# schematic_full.net
KiCad netlist of a schematic drawn in EAGLE
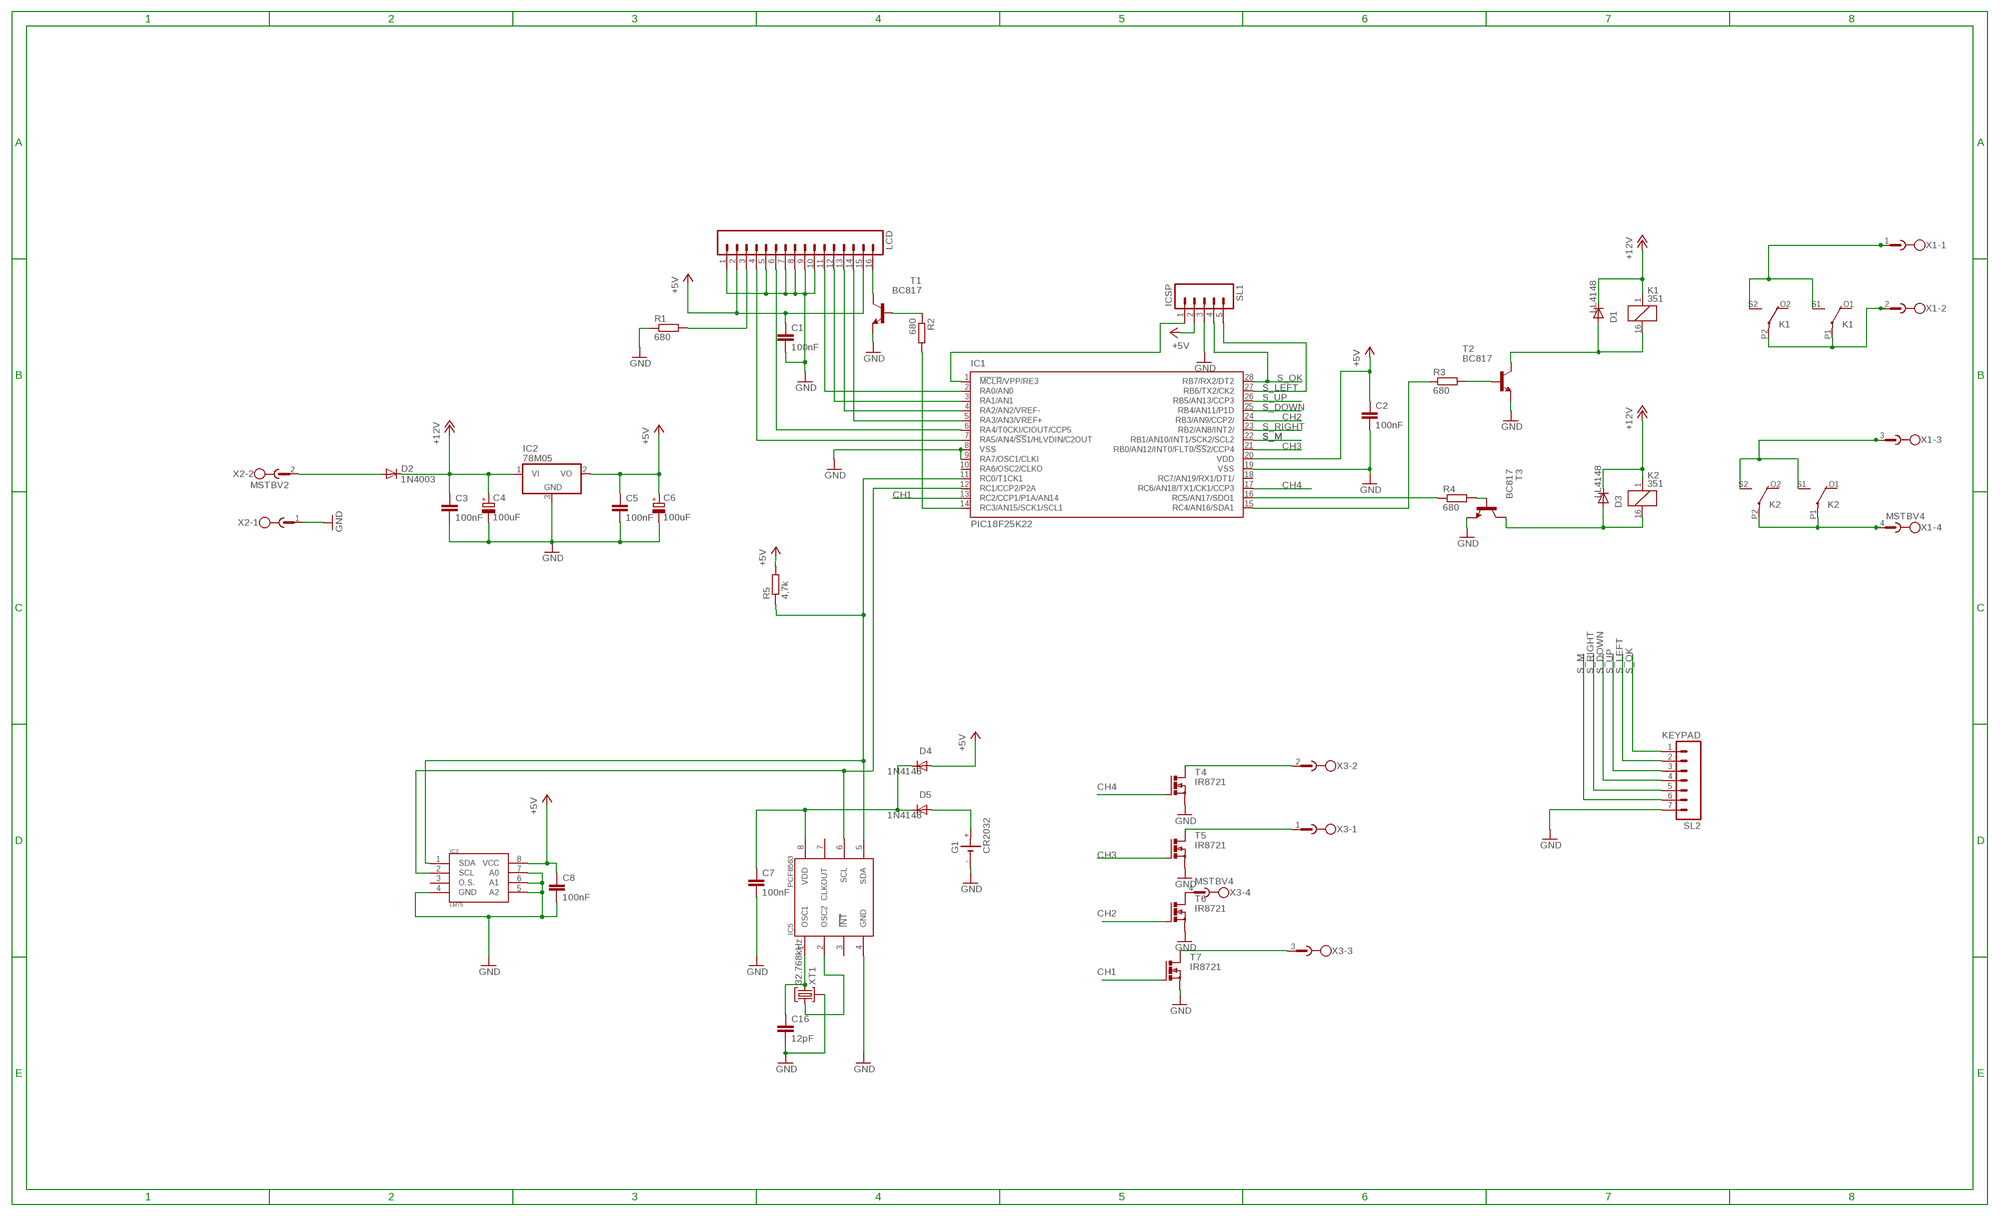
[diagram p0: schematic, sheet 1]

(export (version "E")
  (design (tool "Eeschema 10.0.6"))
  (components
    (comp (ref "C1")
      (value "100nF")
      (footprint "eagle-import:C0805K")
      (libsource (lib "eagle-import") (part "C-EUC0805K"))
    )
    (comp (ref "C2")
      (value "100nF")
      (footprint "eagle-import:C0805K")
      (libsource (lib "eagle-import") (part "C-EUC0805K"))
    )
    (comp (ref "C3")
      (value "100nF")
      (footprint "eagle-import:C0805K")
      (libsource (lib "eagle-import") (part "C-EUC0805K"))
    )
    (comp (ref "C4")
      (value "100uF")
      (footprint "eagle-import:E2,5-6E")
      (libsource (lib "eagle-import") (part "CPOL-EUE2,5-6E"))
    )
    (comp (ref "C5")
      (value "100nF")
      (footprint "eagle-import:C0805K")
      (libsource (lib "eagle-import") (part "C-EUC0805K"))
    )
    (comp (ref "C6")
      (value "100uF")
      (footprint "eagle-import:E2,5-6")
      (libsource (lib "eagle-import") (part "CPOL-EUE2.5-6"))
    )
    (comp (ref "C7")
      (value "100nF")
      (footprint "eagle-import:C0805K")
      (libsource (lib "eagle-import") (part "C-EUC0805K"))
    )
    (comp (ref "C8")
      (value "100nF")
      (footprint "eagle-import:C0805K")
      (libsource (lib "eagle-import") (part "C-EUC0805K"))
    )
    (comp (ref "C16")
      (value "12pF")
      (footprint "eagle-import:C0805K")
      (libsource (lib "eagle-import") (part "C-EUC0805K"))
    )
    (comp (ref "D1")
      (value "LL4148")
      (footprint "eagle-import:DO214BA")
      (libsource (lib "eagle-import") (part "DIODE-DO214BA"))
    )
    (comp (ref "D2")
      (value "1N4003")
      (footprint "eagle-import:DO41-10")
      (libsource (lib "eagle-import") (part "1N4933"))
    )
    (comp (ref "D3")
      (value "LL4148")
      (footprint "eagle-import:DO214BA")
      (libsource (lib "eagle-import") (part "DIODE-DO214BA"))
    )
    (comp (ref "D4")
      (value "1N4148")
      (footprint "eagle-import:DO214BA")
      (libsource (lib "eagle-import") (part "DIODE-DO214BA"))
    )
    (comp (ref "D5")
      (value "1N4148")
      (footprint "eagle-import:DO214BA")
      (libsource (lib "eagle-import") (part "DIODE-DO214BA"))
    )
    (comp (ref "G1")
      (value "CR2032")
      (footprint "eagle-import:CR2032")
      (libsource (lib "eagle-import") (part "CR2032"))
    )
    (comp (ref "IC1")
      (value "PIC18F25K22")
      (footprint "eagle-import:SSOP28")
      (libsource (lib "eagle-import") (part "PIC18F25K22/SS-E"))
    )
    (comp (ref "IC2")
      (value "78M05")
      (footprint "eagle-import:TO252")
      (libsource (lib "eagle-import") (part "78DT05"))
    )
    (comp (ref "IC3")
      (value "LM75")
      (footprint "eagle-import:SO08")
      (libsource (lib "eagle-import") (part "LM75"))
    )
    (comp (ref "IC5")
      (value "PCF8563")
      (footprint "eagle-import:SO08")
      (libsource (lib "eagle-import") (part "PCF8563"))
    )
    (comp (ref "K1")
      (value "351")
      (footprint "eagle-import:351")
      (libsource (lib "eagle-import") (part "351"))
    )
    (comp (ref "K2")
      (value "351")
      (footprint "eagle-import:351")
      (libsource (lib "eagle-import") (part "351"))
    )
    (comp (ref "LCD")
      (value "M16")
      (footprint "eagle-import:16P")
      (libsource (lib "eagle-import") (part "M16"))
    )
    (comp (ref "R1")
      (value "680")
      (footprint "eagle-import:M0805")
      (libsource (lib "eagle-import") (part "R-EU_M0805"))
    )
    (comp (ref "R2")
      (value "680")
      (footprint "eagle-import:M0805")
      (libsource (lib "eagle-import") (part "R-EU_M0805"))
    )
    (comp (ref "R3")
      (value "680")
      (footprint "eagle-import:M0805")
      (libsource (lib "eagle-import") (part "R-EU_M0805"))
    )
    (comp (ref "R4")
      (value "680")
      (footprint "eagle-import:M0805")
      (libsource (lib "eagle-import") (part "R-EU_M0805"))
    )
    (comp (ref "R5")
      (value "4,7k")
      (footprint "eagle-import:M0805")
      (libsource (lib "eagle-import") (part "R-EU_M0805"))
    )
    (comp (ref "SL1")
      (value "ICSP")
      (footprint "eagle-import:05P")
      (libsource (lib "eagle-import") (part "M05"))
    )
    (comp (ref "SL2")
      (value "KEYPAD")
      (footprint "eagle-import:07PA")
      (libsource (lib "eagle-import") (part "MA07"))
    )
    (comp (ref "T1")
      (value "BC817")
      (footprint "eagle-import:SOT23-BEC")
      (libsource (lib "eagle-import") (part "BC817SMD-40"))
    )
    (comp (ref "T2")
      (value "BC817")
      (footprint "eagle-import:SOT23-BEC")
      (libsource (lib "eagle-import") (part "BC817SMD-40"))
    )
    (comp (ref "T3")
      (value "BC817")
      (footprint "eagle-import:SOT23-BEC")
      (libsource (lib "eagle-import") (part "BC817SMD-40"))
    )
    (comp (ref "T4")
      (value "IR8721")
      (footprint "eagle-import:TO252")
      (libsource (lib "eagle-import") (part "IRLR120N"))
    )
    (comp (ref "T5")
      (value "IR8721")
      (footprint "eagle-import:TO252")
      (libsource (lib "eagle-import") (part "IRLR120N"))
    )
    (comp (ref "T6")
      (value "IR8721")
      (footprint "eagle-import:TO252")
      (libsource (lib "eagle-import") (part "IRLR120N"))
    )
    (comp (ref "T7")
      (value "IR8721")
      (footprint "eagle-import:TO252")
      (libsource (lib "eagle-import") (part "IRLR120N"))
    )
    (comp (ref "X1")
      (value "MSTBV4")
      (footprint "eagle-import:MSTBV4")
      (fields (field (name "MPN") "MSTBV 2,5/4-GF-5.08"))
      (libsource (lib "eagle-import") (part "MSTBV4"))
    )
    (comp (ref "X2")
      (value "MSTBV2")
      (footprint "eagle-import:MSTBV2")
      (fields (field (name "MPN") "MSTBV 2,5/2-GF-5.08"))
      (libsource (lib "eagle-import") (part "MSTBV2"))
    )
    (comp (ref "X3")
      (value "MSTBV4")
      (footprint "eagle-import:MSTBV4")
      (fields (field (name "MPN") "MSTBV 2,5/4-GF-5.08"))
      (libsource (lib "eagle-import") (part "MSTBV4"))
    )
    (comp (ref "XT1")
      (value "32.768kHz")
      (footprint "eagle-import:XTMINI")
      (libsource (lib "eagle-import") (part "XTMINI"))
    )
  )
  (nets
    (net (code "1") (name "+5V") (class "Default")
      (node (ref "C1") (pin "1") (pinfunction "1_1") (pintype "passive"))
      (node (ref "C2") (pin "1") (pinfunction "1_1") (pintype "passive"))
      (node (ref "C5") (pin "1") (pinfunction "1_1") (pintype "passive"))
      (node (ref "C6") (pin "+") (pinfunction "+_+") (pintype "passive"))
      (node (ref "C8") (pin "1") (pinfunction "1_1") (pintype "passive"))
      (node (ref "D4") (pin "A") (pinfunction "A_A") (pintype "passive"))
      (node (ref "IC1") (pin "20") (pinfunction "VDD_20") (pintype "power_in"))
      (node (ref "IC2") (pin "2") (pinfunction "VO_2") (pintype "passive"))
      (node (ref "IC3") (pin "8") (pinfunction "VCC_8") (pintype "bidirectional"))
      (node (ref "LCD") (pin "15") (pinfunction "15_15") (pintype "passive"))
      (node (ref "LCD") (pin "2") (pinfunction "2_2") (pintype "passive"))
      (node (ref "R5") (pin "2") (pinfunction "2_2") (pintype "passive"))
      (node (ref "SL1") (pin "2") (pinfunction "2_2") (pintype "passive"))
    )
    (net (code "2") (name "+12V") (class "Default")
      (node (ref "C3") (pin "1") (pinfunction "1_1") (pintype "passive"))
      (node (ref "C4") (pin "+") (pinfunction "+_+") (pintype "passive"))
      (node (ref "D1") (pin "C") (pinfunction "C_C") (pintype "passive"))
      (node (ref "D2") (pin "C") (pinfunction "C_C") (pintype "passive"))
      (node (ref "D3") (pin "C") (pinfunction "C_C") (pintype "passive"))
      (node (ref "IC2") (pin "1") (pinfunction "VI_1") (pintype "input"))
      (node (ref "K1") (pin "1") (pinfunction "1_1") (pintype "passive"))
      (node (ref "K2") (pin "1") (pinfunction "1_1") (pintype "passive"))
    )
    (net (code "3") (name "/CH1") (class "Default")
      (node (ref "IC1") (pin "13") (pinfunction "RC2/CCP1/P1A/AN14_13") (pintype "bidirectional"))
      (node (ref "T7") (pin "1") (pinfunction "G_1") (pintype "passive"))
    )
    (net (code "4") (name "/CH2") (class "Default")
      (node (ref "IC1") (pin "24") (pinfunction "RB3/AN9/CCP2/_24") (pintype "bidirectional"))
      (node (ref "T6") (pin "1") (pinfunction "G_1") (pintype "passive"))
    )
    (net (code "5") (name "/CH3") (class "Default")
      (node (ref "IC1") (pin "21") (pinfunction "RB0/AN12/INT0/FLT0/~{SS}2/CCP4_21") (pintype "bidirectional"))
      (node (ref "T5") (pin "1") (pinfunction "G_1") (pintype "passive"))
    )
    (net (code "6") (name "/CH4") (class "Default")
      (node (ref "IC1") (pin "17") (pinfunction "RC6/AN18/TX1/CK1/CCP3_17") (pintype "bidirectional"))
      (node (ref "T4") (pin "1") (pinfunction "G_1") (pintype "passive"))
    )
    (net (code "7") (name "/S_DOWN") (class "Default")
      (node (ref "IC1") (pin "25") (pinfunction "RB4/AN11/P1D_25") (pintype "bidirectional"))
      (node (ref "SL2") (pin "4") (pinfunction "4_4") (pintype "passive"))
    )
    (net (code "8") (name "/S_LEFT") (class "Default")
      (node (ref "IC1") (pin "27") (pinfunction "RB6/TX2/CK2_27") (pintype "bidirectional"))
      (node (ref "SL1") (pin "5") (pinfunction "5_5") (pintype "passive"))
      (node (ref "SL2") (pin "2") (pinfunction "2_2") (pintype "passive"))
    )
    (net (code "9") (name "/S_M") (class "Default")
      (node (ref "IC1") (pin "22") (pinfunction "RB1/AN10/INT1/SCK2/SCL2_22") (pintype "bidirectional"))
      (node (ref "SL2") (pin "6") (pinfunction "6_6") (pintype "passive"))
    )
    (net (code "10") (name "/S_OK") (class "Default")
      (node (ref "IC1") (pin "28") (pinfunction "RB7/RX2/DT2_28") (pintype "bidirectional"))
      (node (ref "SL1") (pin "4") (pinfunction "4_4") (pintype "passive"))
      (node (ref "SL2") (pin "1") (pinfunction "1_1") (pintype "passive"))
    )
    (net (code "11") (name "/S_RIGHT") (class "Default")
      (node (ref "IC1") (pin "23") (pinfunction "RB2/AN8/INT2/_23") (pintype "bidirectional"))
      (node (ref "SL2") (pin "5") (pinfunction "5_5") (pintype "passive"))
    )
    (net (code "12") (name "/S_UP") (class "Default")
      (node (ref "IC1") (pin "26") (pinfunction "RB5/AN13/CCP3_26") (pintype "bidirectional"))
      (node (ref "SL2") (pin "3") (pinfunction "3_3") (pintype "passive"))
    )
    (net (code "13") (name "GND") (class "Default")
      (node (ref "C1") (pin "2") (pinfunction "2_2") (pintype "passive"))
      (node (ref "C16") (pin "2") (pinfunction "2_2") (pintype "passive"))
      (node (ref "C2") (pin "2") (pinfunction "2_2") (pintype "passive"))
      (node (ref "C3") (pin "2") (pinfunction "2_2") (pintype "passive"))
      (node (ref "C4") (pin "-") (pinfunction "-_-") (pintype "passive"))
      (node (ref "C5") (pin "2") (pinfunction "2_2") (pintype "passive"))
      (node (ref "C6") (pin "-") (pinfunction "-_-") (pintype "passive"))
      (node (ref "C7") (pin "2") (pinfunction "2_2") (pintype "passive"))
      (node (ref "C8") (pin "2") (pinfunction "2_2") (pintype "passive"))
      (node (ref "G1") (pin "-") (pinfunction "-_-") (pintype "passive"))
      (node (ref "IC1") (pin "19") (pinfunction "VSS_19") (pintype "power_in"))
      (node (ref "IC1") (pin "8") (pinfunction "VSS_8") (pintype "power_in"))
      (node (ref "IC1") (pin "9") (pinfunction "RA7/OSC1/CLKI_9") (pintype "input"))
      (node (ref "IC2") (pin "3") (pinfunction "GND_3") (pintype "passive"))
      (node (ref "IC3") (pin "4") (pinfunction "GND_4") (pintype "bidirectional"))
      (node (ref "IC3") (pin "5") (pinfunction "A2_5") (pintype "bidirectional"))
      (node (ref "IC3") (pin "6") (pinfunction "A1_6") (pintype "bidirectional"))
      (node (ref "IC3") (pin "7") (pinfunction "A0_7") (pintype "bidirectional"))
      (node (ref "IC5") (pin "4") (pinfunction "GND_4") (pintype "bidirectional"))
      (node (ref "LCD") (pin "1") (pinfunction "1_1") (pintype "passive"))
      (node (ref "LCD") (pin "10") (pinfunction "10_10") (pintype "passive"))
      (node (ref "LCD") (pin "5") (pinfunction "5_5") (pintype "passive"))
      (node (ref "LCD") (pin "7") (pinfunction "7_7") (pintype "passive"))
      (node (ref "LCD") (pin "8") (pinfunction "8_8") (pintype "passive"))
      (node (ref "LCD") (pin "9") (pinfunction "9_9") (pintype "passive"))
      (node (ref "R1") (pin "1") (pinfunction "1_1") (pintype "passive"))
      (node (ref "SL1") (pin "3") (pinfunction "3_3") (pintype "passive"))
      (node (ref "SL2") (pin "7") (pinfunction "7_7") (pintype "passive"))
      (node (ref "T1") (pin "E") (pinfunction "E_E") (pintype "passive"))
      (node (ref "T2") (pin "E") (pinfunction "E_E") (pintype "passive"))
      (node (ref "T3") (pin "E") (pinfunction "E_E") (pintype "passive"))
      (node (ref "T4") (pin "3") (pinfunction "S_3") (pintype "passive"))
      (node (ref "T5") (pin "3") (pinfunction "S_3") (pintype "passive"))
      (node (ref "T6") (pin "3") (pinfunction "S_3") (pintype "passive"))
      (node (ref "T7") (pin "3") (pinfunction "S_3") (pintype "passive"))
      (node (ref "X2") (pin "1") (pinfunction "1_1") (pintype "passive"))
      (node (ref "XT1") (pin "P$3") (pinfunction "3_P$3") (pintype "passive"))
    )
    (net (code "14") (name "Net-(D5-PadA)") (class "Default")
      (node (ref "D5") (pin "A") (pinfunction "A_A") (pintype "passive"))
      (node (ref "G1") (pin "+") (pinfunction "+_+") (pintype "passive"))
    )
    (net (code "15") (name "Net-(IC1-RA0{slash}AN0)") (class "Default")
      (node (ref "IC1") (pin "2") (pinfunction "RA0/AN0_2") (pintype "bidirectional"))
      (node (ref "LCD") (pin "11") (pinfunction "11_11") (pintype "passive"))
    )
    (net (code "16") (name "Net-(IC1-RA1{slash}AN1)") (class "Default")
      (node (ref "IC1") (pin "3") (pinfunction "RA1/AN1_3") (pintype "bidirectional"))
      (node (ref "LCD") (pin "12") (pinfunction "12_12") (pintype "passive"))
    )
    (net (code "17") (name "Net-(IC1-RA2{slash}AN2{slash}VREF-)") (class "Default")
      (node (ref "IC1") (pin "4") (pinfunction "RA2/AN2/VREF-_4") (pintype "bidirectional"))
      (node (ref "LCD") (pin "13") (pinfunction "13_13") (pintype "passive"))
    )
    (net (code "18") (name "Net-(IC1-RA3{slash}AN3{slash}VREF+)") (class "Default")
      (node (ref "IC1") (pin "5") (pinfunction "RA3/AN3/VREF+_5") (pintype "bidirectional"))
      (node (ref "LCD") (pin "14") (pinfunction "14_14") (pintype "passive"))
    )
    (net (code "19") (name "Net-(IC1-RA4{slash}T0CKI{slash}CIOUT{slash}CCP5)") (class "Default")
      (node (ref "IC1") (pin "6") (pinfunction "RA4/T0CKI/CIOUT/CCP5_6") (pintype "bidirectional"))
      (node (ref "LCD") (pin "6") (pinfunction "6_6") (pintype "passive"))
    )
    (net (code "20") (name "Net-(IC1-RA5{slash}AN4{slash}~{SS}1{slash}HLVDIN{slash}C2OUT)") (class "Default")
      (node (ref "IC1") (pin "7") (pinfunction "RA5/AN4/~{SS}1/HLVDIN/C2OUT_7") (pintype "bidirectional"))
      (node (ref "LCD") (pin "4") (pinfunction "4_4") (pintype "passive"))
    )
    (net (code "21") (name "Net-(IC1-RC0{slash}T1CK1)") (class "Default")
      (node (ref "IC1") (pin "11") (pinfunction "RC0/T1CK1_11") (pintype "bidirectional"))
      (node (ref "IC3") (pin "1") (pinfunction "SDA_1") (pintype "bidirectional"))
      (node (ref "IC5") (pin "5") (pinfunction "SDA_5") (pintype "bidirectional"))
      (node (ref "R5") (pin "1") (pinfunction "1_1") (pintype "passive"))
    )
    (net (code "22") (name "Net-(IC1-RC1{slash}CCP2{slash}P2A)") (class "Default")
      (node (ref "IC1") (pin "12") (pinfunction "RC1/CCP2/P2A_12") (pintype "bidirectional"))
      (node (ref "IC3") (pin "2") (pinfunction "SCL_2") (pintype "bidirectional"))
      (node (ref "IC5") (pin "6") (pinfunction "SCL_6") (pintype "bidirectional"))
    )
    (net (code "23") (name "Net-(IC1-RC3{slash}AN15{slash}SCK1{slash}SCL1)") (class "Default")
      (node (ref "IC1") (pin "14") (pinfunction "RC3/AN15/SCK1/SCL1_14") (pintype "bidirectional"))
      (node (ref "R2") (pin "2") (pinfunction "2_2") (pintype "passive"))
    )
    (net (code "24") (name "Net-(IC1-RC4{slash}AN16{slash}SDA1)") (class "Default")
      (node (ref "IC1") (pin "15") (pinfunction "RC4/AN16/SDA1_15") (pintype "bidirectional"))
      (node (ref "R3") (pin "1") (pinfunction "1_1") (pintype "passive"))
    )
    (net (code "25") (name "Net-(IC1-RC5{slash}AN17{slash}SDO1)") (class "Default")
      (node (ref "IC1") (pin "16") (pinfunction "RC5/AN17/SDO1_16") (pintype "bidirectional"))
      (node (ref "R4") (pin "1") (pinfunction "1_1") (pintype "passive"))
    )
    (net (code "26") (name "Net-(IC1-~{MCLR}{slash}VPP{slash}RE3)") (class "Default")
      (node (ref "IC1") (pin "1") (pinfunction "~{MCLR}/VPP/RE3_1") (pintype "input"))
      (node (ref "SL1") (pin "1") (pinfunction "1_1") (pintype "passive"))
    )
    (net (code "27") (name "Net-(IC5-OSC1)") (class "Default")
      (node (ref "C16") (pin "1") (pinfunction "1_1") (pintype "passive"))
      (node (ref "IC5") (pin "1") (pinfunction "OSC1_1") (pintype "bidirectional"))
      (node (ref "XT1") (pin "P$2") (pinfunction "2_P$2") (pintype "passive"))
    )
    (net (code "28") (name "Net-(IC5-OSC2)") (class "Default")
      (node (ref "IC5") (pin "2") (pinfunction "OSC2_2") (pintype "bidirectional"))
      (node (ref "XT1") (pin "P$1") (pinfunction "1_P$1") (pintype "passive"))
    )
    (net (code "29") (name "Net-(IC5-VDD)") (class "Default")
      (node (ref "C7") (pin "1") (pinfunction "1_1") (pintype "passive"))
      (node (ref "D4") (pin "C") (pinfunction "C_C") (pintype "passive"))
      (node (ref "D5") (pin "C") (pinfunction "C_C") (pintype "passive"))
      (node (ref "IC5") (pin "8") (pinfunction "VDD_8") (pintype "bidirectional"))
    )
    (net (code "30") (name "Net-(K1A-2)") (class "Default")
      (node (ref "D1") (pin "A") (pinfunction "A_A") (pintype "passive"))
      (node (ref "K1") (pin "16") (pinfunction "2_16") (pintype "passive"))
      (node (ref "T2") (pin "C") (pinfunction "C_C") (pintype "passive"))
    )
    (net (code "31") (name "Net-(K1B-P)") (class "Default")
      (node (ref "K1") (pin "P1") (pinfunction "P_P1") (pintype "passive"))
      (node (ref "K1") (pin "P2") (pinfunction "P_P2") (pintype "passive"))
      (node (ref "X1") (pin "2") (pinfunction "1_2") (pintype "passive"))
    )
    (net (code "32") (name "Net-(K1B-S)") (class "Default")
      (node (ref "K1") (pin "S1") (pinfunction "S_S1") (pintype "passive"))
      (node (ref "K1") (pin "S2") (pinfunction "S_S2") (pintype "passive"))
      (node (ref "X1") (pin "1") (pinfunction "1_1") (pintype "passive"))
    )
    (net (code "33") (name "Net-(K2A-2)") (class "Default")
      (node (ref "D3") (pin "A") (pinfunction "A_A") (pintype "passive"))
      (node (ref "K2") (pin "16") (pinfunction "2_16") (pintype "passive"))
      (node (ref "T3") (pin "C") (pinfunction "C_C") (pintype "passive"))
    )
    (net (code "34") (name "Net-(K2B-P)") (class "Default")
      (node (ref "K2") (pin "P1") (pinfunction "P_P1") (pintype "passive"))
      (node (ref "K2") (pin "P2") (pinfunction "P_P2") (pintype "passive"))
      (node (ref "X1") (pin "4") (pinfunction "1_4") (pintype "passive"))
    )
    (net (code "35") (name "Net-(K2B-S)") (class "Default")
      (node (ref "K2") (pin "S1") (pinfunction "S_S1") (pintype "passive"))
      (node (ref "K2") (pin "S2") (pinfunction "S_S2") (pintype "passive"))
      (node (ref "X1") (pin "3") (pinfunction "1_3") (pintype "passive"))
    )
    (net (code "36") (name "Net-(LCD-Pad3)") (class "Default")
      (node (ref "LCD") (pin "3") (pinfunction "3_3") (pintype "passive"))
      (node (ref "R1") (pin "2") (pinfunction "2_2") (pintype "passive"))
    )
    (net (code "37") (name "Net-(LCD-Pad16)") (class "Default")
      (node (ref "LCD") (pin "16") (pinfunction "16_16") (pintype "passive"))
      (node (ref "T1") (pin "C") (pinfunction "C_C") (pintype "passive"))
    )
    (net (code "38") (name "Net-(R2-Pad1)") (class "Default")
      (node (ref "R2") (pin "1") (pinfunction "1_1") (pintype "passive"))
      (node (ref "T1") (pin "B") (pinfunction "B_B") (pintype "passive"))
    )
    (net (code "39") (name "Net-(R3-Pad2)") (class "Default")
      (node (ref "R3") (pin "2") (pinfunction "2_2") (pintype "passive"))
      (node (ref "T2") (pin "B") (pinfunction "B_B") (pintype "passive"))
    )
    (net (code "40") (name "Net-(R4-Pad2)") (class "Default")
      (node (ref "R4") (pin "2") (pinfunction "2_2") (pintype "passive"))
      (node (ref "T3") (pin "B") (pinfunction "B_B") (pintype "passive"))
    )
    (net (code "41") (name "Net-(T4-D)") (class "Default")
      (node (ref "T4") (pin "2") (pinfunction "D_2") (pintype "passive"))
      (node (ref "X3") (pin "2") (pinfunction "1_2") (pintype "passive"))
    )
    (net (code "42") (name "Net-(T5-D)") (class "Default")
      (node (ref "T5") (pin "2") (pinfunction "D_2") (pintype "passive"))
      (node (ref "X3") (pin "1") (pinfunction "1_1") (pintype "passive"))
    )
    (net (code "43") (name "Net-(T6-D)") (class "Default")
      (node (ref "T6") (pin "2") (pinfunction "D_2") (pintype "passive"))
      (node (ref "X3") (pin "4") (pinfunction "1_4") (pintype "passive"))
    )
    (net (code "44") (name "Net-(T7-D)") (class "Default")
      (node (ref "T7") (pin "2") (pinfunction "D_2") (pintype "passive"))
      (node (ref "X3") (pin "3") (pinfunction "1_3") (pintype "passive"))
    )
    (net (code "45") (name "Net-(X2B-1)") (class "Default")
      (node (ref "D2") (pin "A") (pinfunction "A_A") (pintype "passive"))
      (node (ref "X2") (pin "2") (pinfunction "1_2") (pintype "passive"))
    )
    (net (code "46") (name "unconnected-(IC1-RA6{slash}OSC2{slash}CLKO-Pad10)") (class "Default")
      (node (ref "IC1") (pin "10") (pinfunction "RA6/OSC2/CLKO_10") (pintype "output"))
    )
    (net (code "47") (name "unconnected-(IC1-RC7{slash}AN19{slash}RX1{slash}DT1{slash}-Pad18)") (class "Default")
      (node (ref "IC1") (pin "18") (pinfunction "RC7/AN19/RX1/DT1/_18") (pintype "bidirectional"))
    )
    (net (code "48") (name "unconnected-(IC3-O.S.-Pad3)") (class "Default")
      (node (ref "IC3") (pin "3") (pinfunction "O.S._3") (pintype "bidirectional"))
    )
    (net (code "49") (name "unconnected-(IC5-CLKOUT-Pad7)") (class "Default")
      (node (ref "IC5") (pin "7") (pinfunction "CLKOUT_7") (pintype "bidirectional"))
    )
    (net (code "50") (name "unconnected-(IC5-INT-Pad3)") (class "Default")
      (node (ref "IC5") (pin "3") (pinfunction "INT_3") (pintype "bidirectional"))
    )
    (net (code "51") (name "unconnected-(K1B-O-PadO1)") (class "Default")
      (node (ref "K1") (pin "O1") (pinfunction "O_O1") (pintype "passive"))
    )
    (net (code "52") (name "unconnected-(K1C-O-PadO2)") (class "Default")
      (node (ref "K1") (pin "O2") (pinfunction "O_O2") (pintype "passive"))
    )
    (net (code "53") (name "unconnected-(K2B-O-PadO1)") (class "Default")
      (node (ref "K2") (pin "O1") (pinfunction "O_O1") (pintype "passive"))
    )
    (net (code "54") (name "unconnected-(K2C-O-PadO2)") (class "Default")
      (node (ref "K2") (pin "O2") (pinfunction "O_O2") (pintype "passive"))
    )
  )
)
